# RGBW_controller.net
KiCad netlist of a schematic drawn in EAGLE
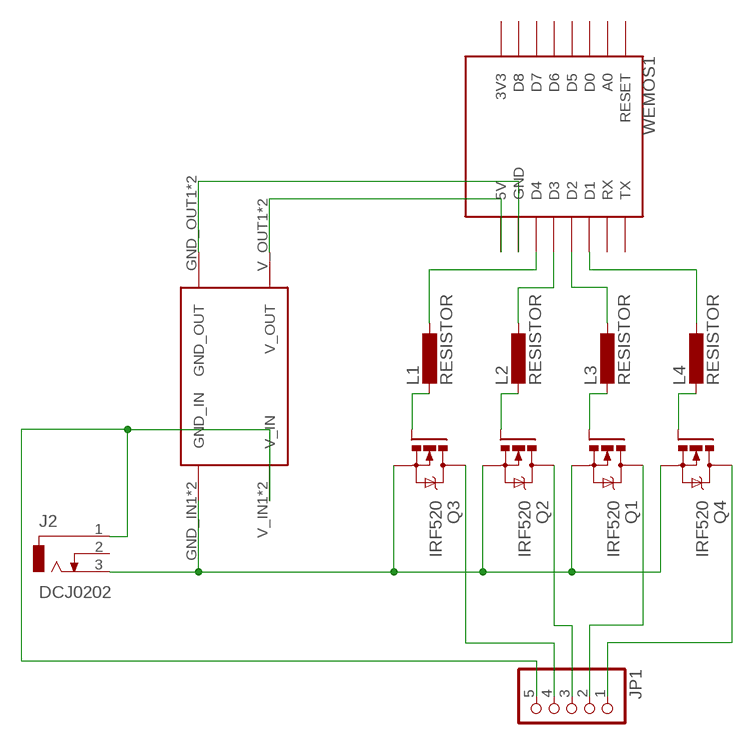
[diagram p0: schematic, sheet 1]

(export (version "E")
  (design (tool "Eeschema 10.0.6"))
  (components
    (comp (ref "J2")
      (value "DCJ0202")
      (footprint "eagle-import:DCJ0202")
      (libsource (lib "eagle-import") (part "DCJ0202"))
    )
    (comp (ref "JP1")
      (value "PINHD-1X5")
      (footprint "eagle-import:1X05")
      (libsource (lib "eagle-import") (part "PINHD-1X5"))
    )
    (comp (ref "L1")
      (value "RESISTOR")
      (footprint "eagle-import:RESISTOR")
      (libsource (lib "eagle-import") (part "RESISTOR"))
    )
    (comp (ref "L2")
      (value "RESISTOR")
      (footprint "eagle-import:RESISTOR")
      (libsource (lib "eagle-import") (part "RESISTOR"))
    )
    (comp (ref "L3")
      (value "RESISTOR")
      (footprint "eagle-import:RESISTOR")
      (libsource (lib "eagle-import") (part "RESISTOR"))
    )
    (comp (ref "L4")
      (value "RESISTOR")
      (footprint "eagle-import:RESISTOR")
      (libsource (lib "eagle-import") (part "RESISTOR"))
    )
    (comp (ref "Q1")
      (value "IRF520")
      (footprint "eagle-import:TO220BV")
      (libsource (lib "eagle-import") (part "IRF520"))
    )
    (comp (ref "Q2")
      (value "IRF520")
      (footprint "eagle-import:TO220BV")
      (libsource (lib "eagle-import") (part "IRF520"))
    )
    (comp (ref "Q3")
      (value "IRF520")
      (footprint "eagle-import:TO220BV")
      (libsource (lib "eagle-import") (part "IRF520"))
    )
    (comp (ref "Q4")
      (value "IRF520")
      (footprint "eagle-import:TO220BV")
      (libsource (lib "eagle-import") (part "IRF520"))
    )
    (comp (ref "U$1")
      (value "DC-DC-CONVERTER")
      (footprint "eagle-import:DC-DC-CONVERTER")
      (libsource (lib "eagle-import") (part "DC-DC-CONVERTER"))
    )
    (comp (ref "WEMOS1")
      (value "WEMOS-D1-MINI")
      (footprint "eagle-import:WEMOS-D1-MINI")
      (libsource (lib "eagle-import") (part "WEMOS-D1-MINI"))
    )
  )
  (nets
    (net (code "1") (name "Net-(J2-Pad1)") (class "Default")
      (node (ref "J2") (pin "1") (pinfunction "1_1") (pintype "passive"))
      (node (ref "JP1") (pin "5") (pinfunction "5_5") (pintype "passive"))
      (node (ref "U$1") (pin "V_IN1") (pinfunction "V_IN_V_IN1") (pintype "bidirectional"))
      (node (ref "U$1") (pin "V_IN2") (pinfunction "V_IN_V_IN2") (pintype "bidirectional"))
    )
    (net (code "2") (name "Net-(J2-Pad3)") (class "Default")
      (node (ref "J2") (pin "3") (pinfunction "3_3") (pintype "passive"))
      (node (ref "Q1") (pin "S") (pinfunction "S_S") (pintype "passive"))
      (node (ref "Q2") (pin "S") (pinfunction "S_S") (pintype "passive"))
      (node (ref "Q3") (pin "S") (pinfunction "S_S") (pintype "passive"))
      (node (ref "Q4") (pin "S") (pinfunction "S_S") (pintype "passive"))
      (node (ref "U$1") (pin "GND_IN1") (pinfunction "GND_IN_GND_IN1") (pintype "bidirectional"))
      (node (ref "U$1") (pin "GND_IN2") (pinfunction "GND_IN_GND_IN2") (pintype "bidirectional"))
    )
    (net (code "3") (name "Net-(JP1-Pad1)") (class "Default")
      (node (ref "JP1") (pin "1") (pinfunction "1_1") (pintype "passive"))
      (node (ref "Q4") (pin "D") (pinfunction "D_D") (pintype "passive"))
    )
    (net (code "4") (name "Net-(JP1-Pad2)") (class "Default")
      (node (ref "JP1") (pin "2") (pinfunction "2_2") (pintype "passive"))
      (node (ref "Q1") (pin "D") (pinfunction "D_D") (pintype "passive"))
    )
    (net (code "5") (name "Net-(JP1-Pad3)") (class "Default")
      (node (ref "JP1") (pin "3") (pinfunction "3_3") (pintype "passive"))
      (node (ref "Q2") (pin "D") (pinfunction "D_D") (pintype "passive"))
    )
    (net (code "6") (name "Net-(JP1-Pad4)") (class "Default")
      (node (ref "JP1") (pin "4") (pinfunction "4_4") (pintype "passive"))
      (node (ref "Q3") (pin "D") (pinfunction "D_D") (pintype "passive"))
    )
    (net (code "7") (name "Net-(L1-Pad1)") (class "Default")
      (node (ref "L1") (pin "1") (pinfunction "1_1") (pintype "passive"))
      (node (ref "WEMOS1") (pin "D4") (pinfunction "D4_D4") (pintype "bidirectional"))
    )
    (net (code "8") (name "Net-(L1-Pad2)") (class "Default")
      (node (ref "L1") (pin "2") (pinfunction "2_2") (pintype "passive"))
      (node (ref "Q3") (pin "G") (pinfunction "G_G") (pintype "passive"))
    )
    (net (code "9") (name "Net-(L2-Pad1)") (class "Default")
      (node (ref "L2") (pin "1") (pinfunction "1_1") (pintype "passive"))
      (node (ref "WEMOS1") (pin "D3") (pinfunction "D3_D3") (pintype "bidirectional"))
    )
    (net (code "10") (name "Net-(L2-Pad2)") (class "Default")
      (node (ref "L2") (pin "2") (pinfunction "2_2") (pintype "passive"))
      (node (ref "Q2") (pin "G") (pinfunction "G_G") (pintype "passive"))
    )
    (net (code "11") (name "Net-(L3-Pad1)") (class "Default")
      (node (ref "L3") (pin "1") (pinfunction "1_1") (pintype "passive"))
      (node (ref "WEMOS1") (pin "D2") (pinfunction "D2_D2") (pintype "bidirectional"))
    )
    (net (code "12") (name "Net-(L3-Pad2)") (class "Default")
      (node (ref "L3") (pin "2") (pinfunction "2_2") (pintype "passive"))
      (node (ref "Q1") (pin "G") (pinfunction "G_G") (pintype "passive"))
    )
    (net (code "13") (name "Net-(L4-Pad1)") (class "Default")
      (node (ref "L4") (pin "1") (pinfunction "1_1") (pintype "passive"))
      (node (ref "WEMOS1") (pin "D1") (pinfunction "D1_D1") (pintype "bidirectional"))
    )
    (net (code "14") (name "Net-(L4-Pad2)") (class "Default")
      (node (ref "L4") (pin "2") (pinfunction "2_2") (pintype "passive"))
      (node (ref "Q4") (pin "G") (pinfunction "G_G") (pintype "passive"))
    )
    (net (code "15") (name "Net-(U$1-GND_OUT-PadGND_OUT1)") (class "Default")
      (node (ref "U$1") (pin "GND_OUT1") (pinfunction "GND_OUT_GND_OUT1") (pintype "bidirectional"))
      (node (ref "U$1") (pin "GND_OUT2") (pinfunction "GND_OUT_GND_OUT2") (pintype "bidirectional"))
      (node (ref "WEMOS1") (pin "GND") (pinfunction "GND_GND") (pintype "bidirectional"))
    )
    (net (code "16") (name "Net-(U$1-V_OUT-PadV_OUT1)") (class "Default")
      (node (ref "U$1") (pin "V_OUT1") (pinfunction "V_OUT_V_OUT1") (pintype "bidirectional"))
      (node (ref "U$1") (pin "V_OUT2") (pinfunction "V_OUT_V_OUT2") (pintype "bidirectional"))
      (node (ref "WEMOS1") (pin "5V") (pinfunction "5V_5V") (pintype "bidirectional"))
    )
    (net (code "17") (name "unconnected-(J2-Pad2)") (class "Default")
      (node (ref "J2") (pin "2") (pinfunction "2_2") (pintype "passive"))
    )
    (net (code "18") (name "unconnected-(WEMOS1-Pad3V3)") (class "Default")
      (node (ref "WEMOS1") (pin "3V3") (pinfunction "3V3_3V3") (pintype "bidirectional"))
    )
    (net (code "19") (name "unconnected-(WEMOS1-PadA0)") (class "Default")
      (node (ref "WEMOS1") (pin "A0") (pinfunction "A0_A0") (pintype "bidirectional"))
    )
    (net (code "20") (name "unconnected-(WEMOS1-PadD0)") (class "Default")
      (node (ref "WEMOS1") (pin "D0") (pinfunction "D0_D0") (pintype "bidirectional"))
    )
    (net (code "21") (name "unconnected-(WEMOS1-PadD5)") (class "Default")
      (node (ref "WEMOS1") (pin "D5") (pinfunction "D5_D5") (pintype "bidirectional"))
    )
    (net (code "22") (name "unconnected-(WEMOS1-PadD6)") (class "Default")
      (node (ref "WEMOS1") (pin "D6") (pinfunction "D6_D6") (pintype "bidirectional"))
    )
    (net (code "23") (name "unconnected-(WEMOS1-PadD7)") (class "Default")
      (node (ref "WEMOS1") (pin "D7") (pinfunction "D7_D7") (pintype "bidirectional"))
    )
    (net (code "24") (name "unconnected-(WEMOS1-PadD8)") (class "Default")
      (node (ref "WEMOS1") (pin "D8") (pinfunction "D8_D8") (pintype "bidirectional"))
    )
    (net (code "25") (name "unconnected-(WEMOS1-PadRESET)") (class "Default")
      (node (ref "WEMOS1") (pin "RESET") (pinfunction "RESET_RESET") (pintype "bidirectional"))
    )
    (net (code "26") (name "unconnected-(WEMOS1-PadRX)") (class "Default")
      (node (ref "WEMOS1") (pin "RX") (pinfunction "RX_RX") (pintype "bidirectional"))
    )
    (net (code "27") (name "unconnected-(WEMOS1-PadTX)") (class "Default")
      (node (ref "WEMOS1") (pin "TX") (pinfunction "TX_TX") (pintype "bidirectional"))
    )
  )
)
